# color_sensor.net
KiCad netlist of a schematic drawn in EAGLE
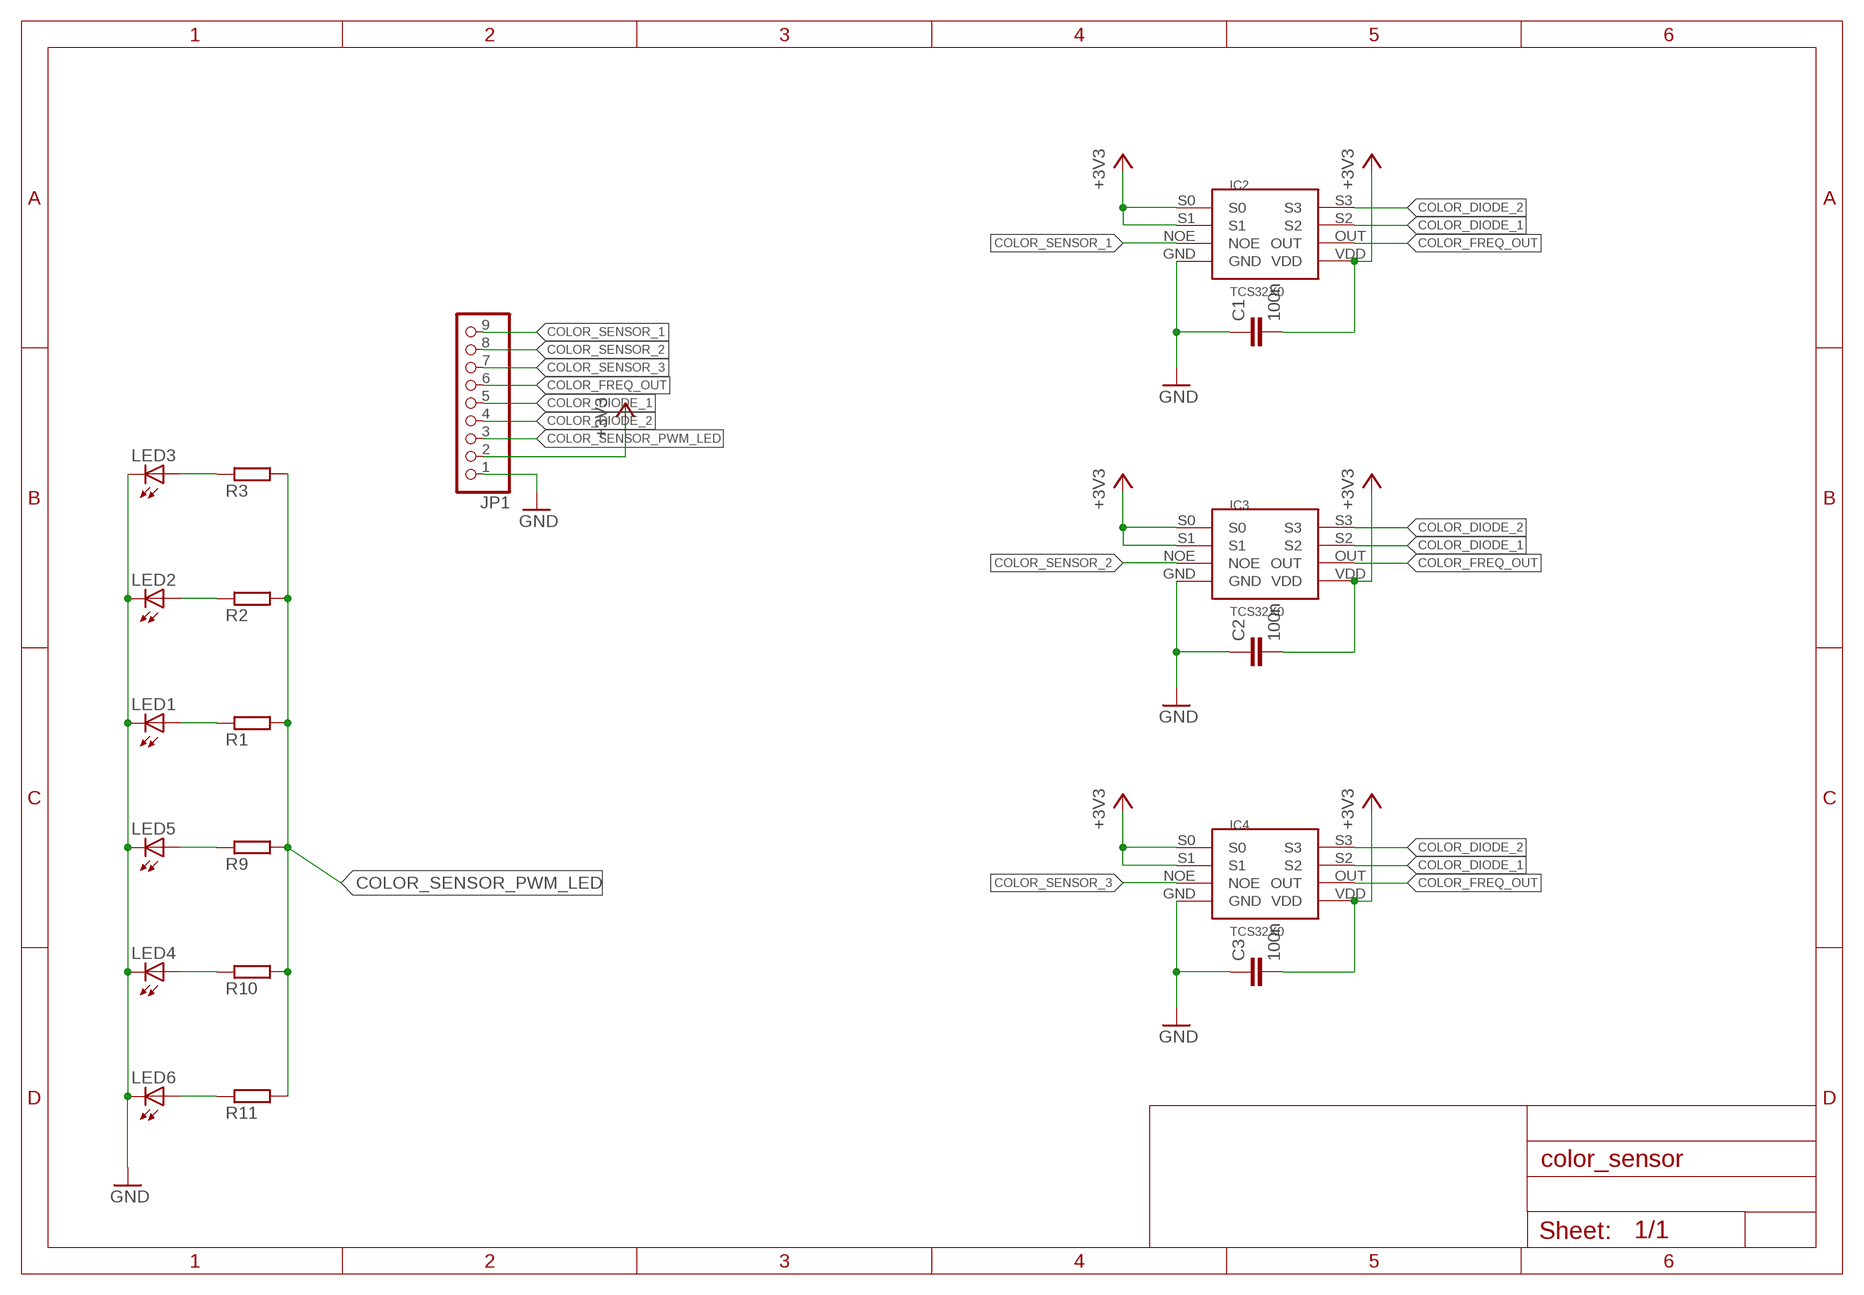
[diagram p0: schematic, sheet 1]

(export (version "E")
  (design (tool "Eeschema 10.0.6"))
  (components
    (comp (ref "C1")
      (value "100n")
      (footprint "eagle-import:C0805")
      (libsource (lib "eagle-import") (part "C-EUC0805"))
    )
    (comp (ref "C2")
      (value "100n")
      (footprint "eagle-import:C0805")
      (libsource (lib "eagle-import") (part "C-EUC0805"))
    )
    (comp (ref "C3")
      (value "100n")
      (footprint "eagle-import:C0805")
      (libsource (lib "eagle-import") (part "C-EUC0805"))
    )
    (comp (ref "IC2")
      (value "TCS32X0")
      (footprint "eagle-import:TCS32X0")
      (libsource (lib "eagle-import") (part "TCS32X0"))
    )
    (comp (ref "IC3")
      (value "TCS32X0")
      (footprint "eagle-import:TCS32X0")
      (libsource (lib "eagle-import") (part "TCS32X0"))
    )
    (comp (ref "IC4")
      (value "TCS32X0")
      (footprint "eagle-import:TCS32X0")
      (libsource (lib "eagle-import") (part "TCS32X0"))
    )
    (comp (ref "JP1")
      (value "PINHD-1X9")
      (footprint "eagle-import:1X09")
      (libsource (lib "eagle-import") (part "PINHD-1X9"))
    )
    (comp (ref "LED1")
      (value "NFSG036BT")
      (footprint "eagle-import:NFSG036BT")
      (libsource (lib "eagle-import") (part "NFSG036BT"))
    )
    (comp (ref "LED2")
      (value "NFSG036BT")
      (footprint "eagle-import:NFSG036BT")
      (libsource (lib "eagle-import") (part "NFSG036BT"))
    )
    (comp (ref "LED3")
      (value "NFSG036BT")
      (footprint "eagle-import:NFSG036BT")
      (libsource (lib "eagle-import") (part "NFSG036BT"))
    )
    (comp (ref "LED4")
      (value "NFSG036BT")
      (footprint "eagle-import:NFSG036BT")
      (libsource (lib "eagle-import") (part "NFSG036BT"))
    )
    (comp (ref "LED5")
      (value "NFSG036BT")
      (footprint "eagle-import:NFSG036BT")
      (libsource (lib "eagle-import") (part "NFSG036BT"))
    )
    (comp (ref "LED6")
      (value "NFSG036BT")
      (footprint "eagle-import:NFSG036BT")
      (libsource (lib "eagle-import") (part "NFSG036BT"))
    )
    (comp (ref "R1")
      (value "R-EU_M0805")
      (footprint "eagle-import:M0805")
      (libsource (lib "eagle-import") (part "R-EU_M0805"))
    )
    (comp (ref "R2")
      (value "R-EU_M0805")
      (footprint "eagle-import:M0805")
      (libsource (lib "eagle-import") (part "R-EU_M0805"))
    )
    (comp (ref "R3")
      (value "R-EU_M0805")
      (footprint "eagle-import:M0805")
      (libsource (lib "eagle-import") (part "R-EU_M0805"))
    )
    (comp (ref "R9")
      (value "R-EU_M0805")
      (footprint "eagle-import:M0805")
      (libsource (lib "eagle-import") (part "R-EU_M0805"))
    )
    (comp (ref "R10")
      (value "R-EU_M0805")
      (footprint "eagle-import:M0805")
      (libsource (lib "eagle-import") (part "R-EU_M0805"))
    )
    (comp (ref "R11")
      (value "R-EU_M0805")
      (footprint "eagle-import:M0805")
      (libsource (lib "eagle-import") (part "R-EU_M0805"))
    )
  )
  (nets
    (net (code "1") (name "+3V3") (class "Default")
      (node (ref "C1") (pin "2") (pinfunction "2_2") (pintype "passive"))
      (node (ref "C2") (pin "2") (pinfunction "2_2") (pintype "passive"))
      (node (ref "C3") (pin "2") (pinfunction "2_2") (pintype "passive"))
      (node (ref "IC2") (pin "S0") (pinfunction "S0_S0") (pintype "input"))
      (node (ref "IC2") (pin "S1") (pinfunction "S1_S1") (pintype "input"))
      (node (ref "IC2") (pin "VDD") (pinfunction "VDD_VDD") (pintype "power_in"))
      (node (ref "IC3") (pin "S0") (pinfunction "S0_S0") (pintype "input"))
      (node (ref "IC3") (pin "S1") (pinfunction "S1_S1") (pintype "input"))
      (node (ref "IC3") (pin "VDD") (pinfunction "VDD_VDD") (pintype "power_in"))
      (node (ref "IC4") (pin "S0") (pinfunction "S0_S0") (pintype "input"))
      (node (ref "IC4") (pin "S1") (pinfunction "S1_S1") (pintype "input"))
      (node (ref "IC4") (pin "VDD") (pinfunction "VDD_VDD") (pintype "power_in"))
      (node (ref "JP1") (pin "2") (pinfunction "2_2") (pintype "passive"))
    )
    (net (code "2") (name "COLOR_DIODE_1") (class "Default")
      (node (ref "IC2") (pin "S2") (pinfunction "S2_S2") (pintype "input"))
      (node (ref "IC3") (pin "S2") (pinfunction "S2_S2") (pintype "input"))
      (node (ref "IC4") (pin "S2") (pinfunction "S2_S2") (pintype "input"))
      (node (ref "JP1") (pin "5") (pinfunction "5_5") (pintype "passive"))
    )
    (net (code "3") (name "COLOR_DIODE_2") (class "Default")
      (node (ref "IC2") (pin "S3") (pinfunction "S3_S3") (pintype "input"))
      (node (ref "IC3") (pin "S3") (pinfunction "S3_S3") (pintype "input"))
      (node (ref "IC4") (pin "S3") (pinfunction "S3_S3") (pintype "input"))
      (node (ref "JP1") (pin "4") (pinfunction "4_4") (pintype "passive"))
    )
    (net (code "4") (name "COLOR_FREQ_OUT") (class "Default")
      (node (ref "IC2") (pin "OUT") (pinfunction "OUT_OUT") (pintype "output"))
      (node (ref "IC3") (pin "OUT") (pinfunction "OUT_OUT") (pintype "output"))
      (node (ref "IC4") (pin "OUT") (pinfunction "OUT_OUT") (pintype "output"))
      (node (ref "JP1") (pin "6") (pinfunction "6_6") (pintype "passive"))
    )
    (net (code "5") (name "COLOR_SENSOR_1") (class "Default")
      (node (ref "IC2") (pin "NOE") (pinfunction "NOE_NOE") (pintype "output"))
      (node (ref "JP1") (pin "9") (pinfunction "9_9") (pintype "passive"))
    )
    (net (code "6") (name "COLOR_SENSOR_2") (class "Default")
      (node (ref "IC3") (pin "NOE") (pinfunction "NOE_NOE") (pintype "output"))
      (node (ref "JP1") (pin "8") (pinfunction "8_8") (pintype "passive"))
    )
    (net (code "7") (name "COLOR_SENSOR_3") (class "Default")
      (node (ref "IC4") (pin "NOE") (pinfunction "NOE_NOE") (pintype "output"))
      (node (ref "JP1") (pin "7") (pinfunction "7_7") (pintype "passive"))
    )
    (net (code "8") (name "COLOR_SENSOR_PWM_LED") (class "Default")
      (node (ref "JP1") (pin "3") (pinfunction "3_3") (pintype "passive"))
      (node (ref "R1") (pin "2") (pinfunction "2_2") (pintype "passive"))
      (node (ref "R10") (pin "2") (pinfunction "2_2") (pintype "passive"))
      (node (ref "R11") (pin "2") (pinfunction "2_2") (pintype "passive"))
      (node (ref "R2") (pin "2") (pinfunction "2_2") (pintype "passive"))
      (node (ref "R3") (pin "2") (pinfunction "2_2") (pintype "passive"))
      (node (ref "R9") (pin "2") (pinfunction "2_2") (pintype "passive"))
    )
    (net (code "9") (name "GND") (class "Default")
      (node (ref "C1") (pin "1") (pinfunction "1_1") (pintype "passive"))
      (node (ref "C2") (pin "1") (pinfunction "1_1") (pintype "passive"))
      (node (ref "C3") (pin "1") (pinfunction "1_1") (pintype "passive"))
      (node (ref "IC2") (pin "GND") (pinfunction "GND_GND") (pintype "power_in"))
      (node (ref "IC3") (pin "GND") (pinfunction "GND_GND") (pintype "power_in"))
      (node (ref "IC4") (pin "GND") (pinfunction "GND_GND") (pintype "power_in"))
      (node (ref "JP1") (pin "1") (pinfunction "1_1") (pintype "passive"))
      (node (ref "LED1") (pin "C") (pinfunction "C_C") (pintype "passive"))
      (node (ref "LED2") (pin "C") (pinfunction "C_C") (pintype "passive"))
      (node (ref "LED3") (pin "C") (pinfunction "C_C") (pintype "passive"))
      (node (ref "LED4") (pin "C") (pinfunction "C_C") (pintype "passive"))
      (node (ref "LED5") (pin "C") (pinfunction "C_C") (pintype "passive"))
      (node (ref "LED6") (pin "C") (pinfunction "C_C") (pintype "passive"))
    )
    (net (code "10") (name "Net-(LED1-PadA)") (class "Default")
      (node (ref "LED1") (pin "A") (pinfunction "A_A") (pintype "passive"))
      (node (ref "R1") (pin "1") (pinfunction "1_1") (pintype "passive"))
    )
    (net (code "11") (name "Net-(LED2-PadA)") (class "Default")
      (node (ref "LED2") (pin "A") (pinfunction "A_A") (pintype "passive"))
      (node (ref "R2") (pin "1") (pinfunction "1_1") (pintype "passive"))
    )
    (net (code "12") (name "Net-(LED3-PadA)") (class "Default")
      (node (ref "LED3") (pin "A") (pinfunction "A_A") (pintype "passive"))
      (node (ref "R3") (pin "1") (pinfunction "1_1") (pintype "passive"))
    )
    (net (code "13") (name "Net-(LED4-PadA)") (class "Default")
      (node (ref "LED4") (pin "A") (pinfunction "A_A") (pintype "passive"))
      (node (ref "R10") (pin "1") (pinfunction "1_1") (pintype "passive"))
    )
    (net (code "14") (name "Net-(LED5-PadA)") (class "Default")
      (node (ref "LED5") (pin "A") (pinfunction "A_A") (pintype "passive"))
      (node (ref "R9") (pin "1") (pinfunction "1_1") (pintype "passive"))
    )
    (net (code "15") (name "Net-(LED6-PadA)") (class "Default")
      (node (ref "LED6") (pin "A") (pinfunction "A_A") (pintype "passive"))
      (node (ref "R11") (pin "1") (pinfunction "1_1") (pintype "passive"))
    )
  )
)
